# W1209_PIC.net
KiCad netlist of a schematic drawn in EAGLE
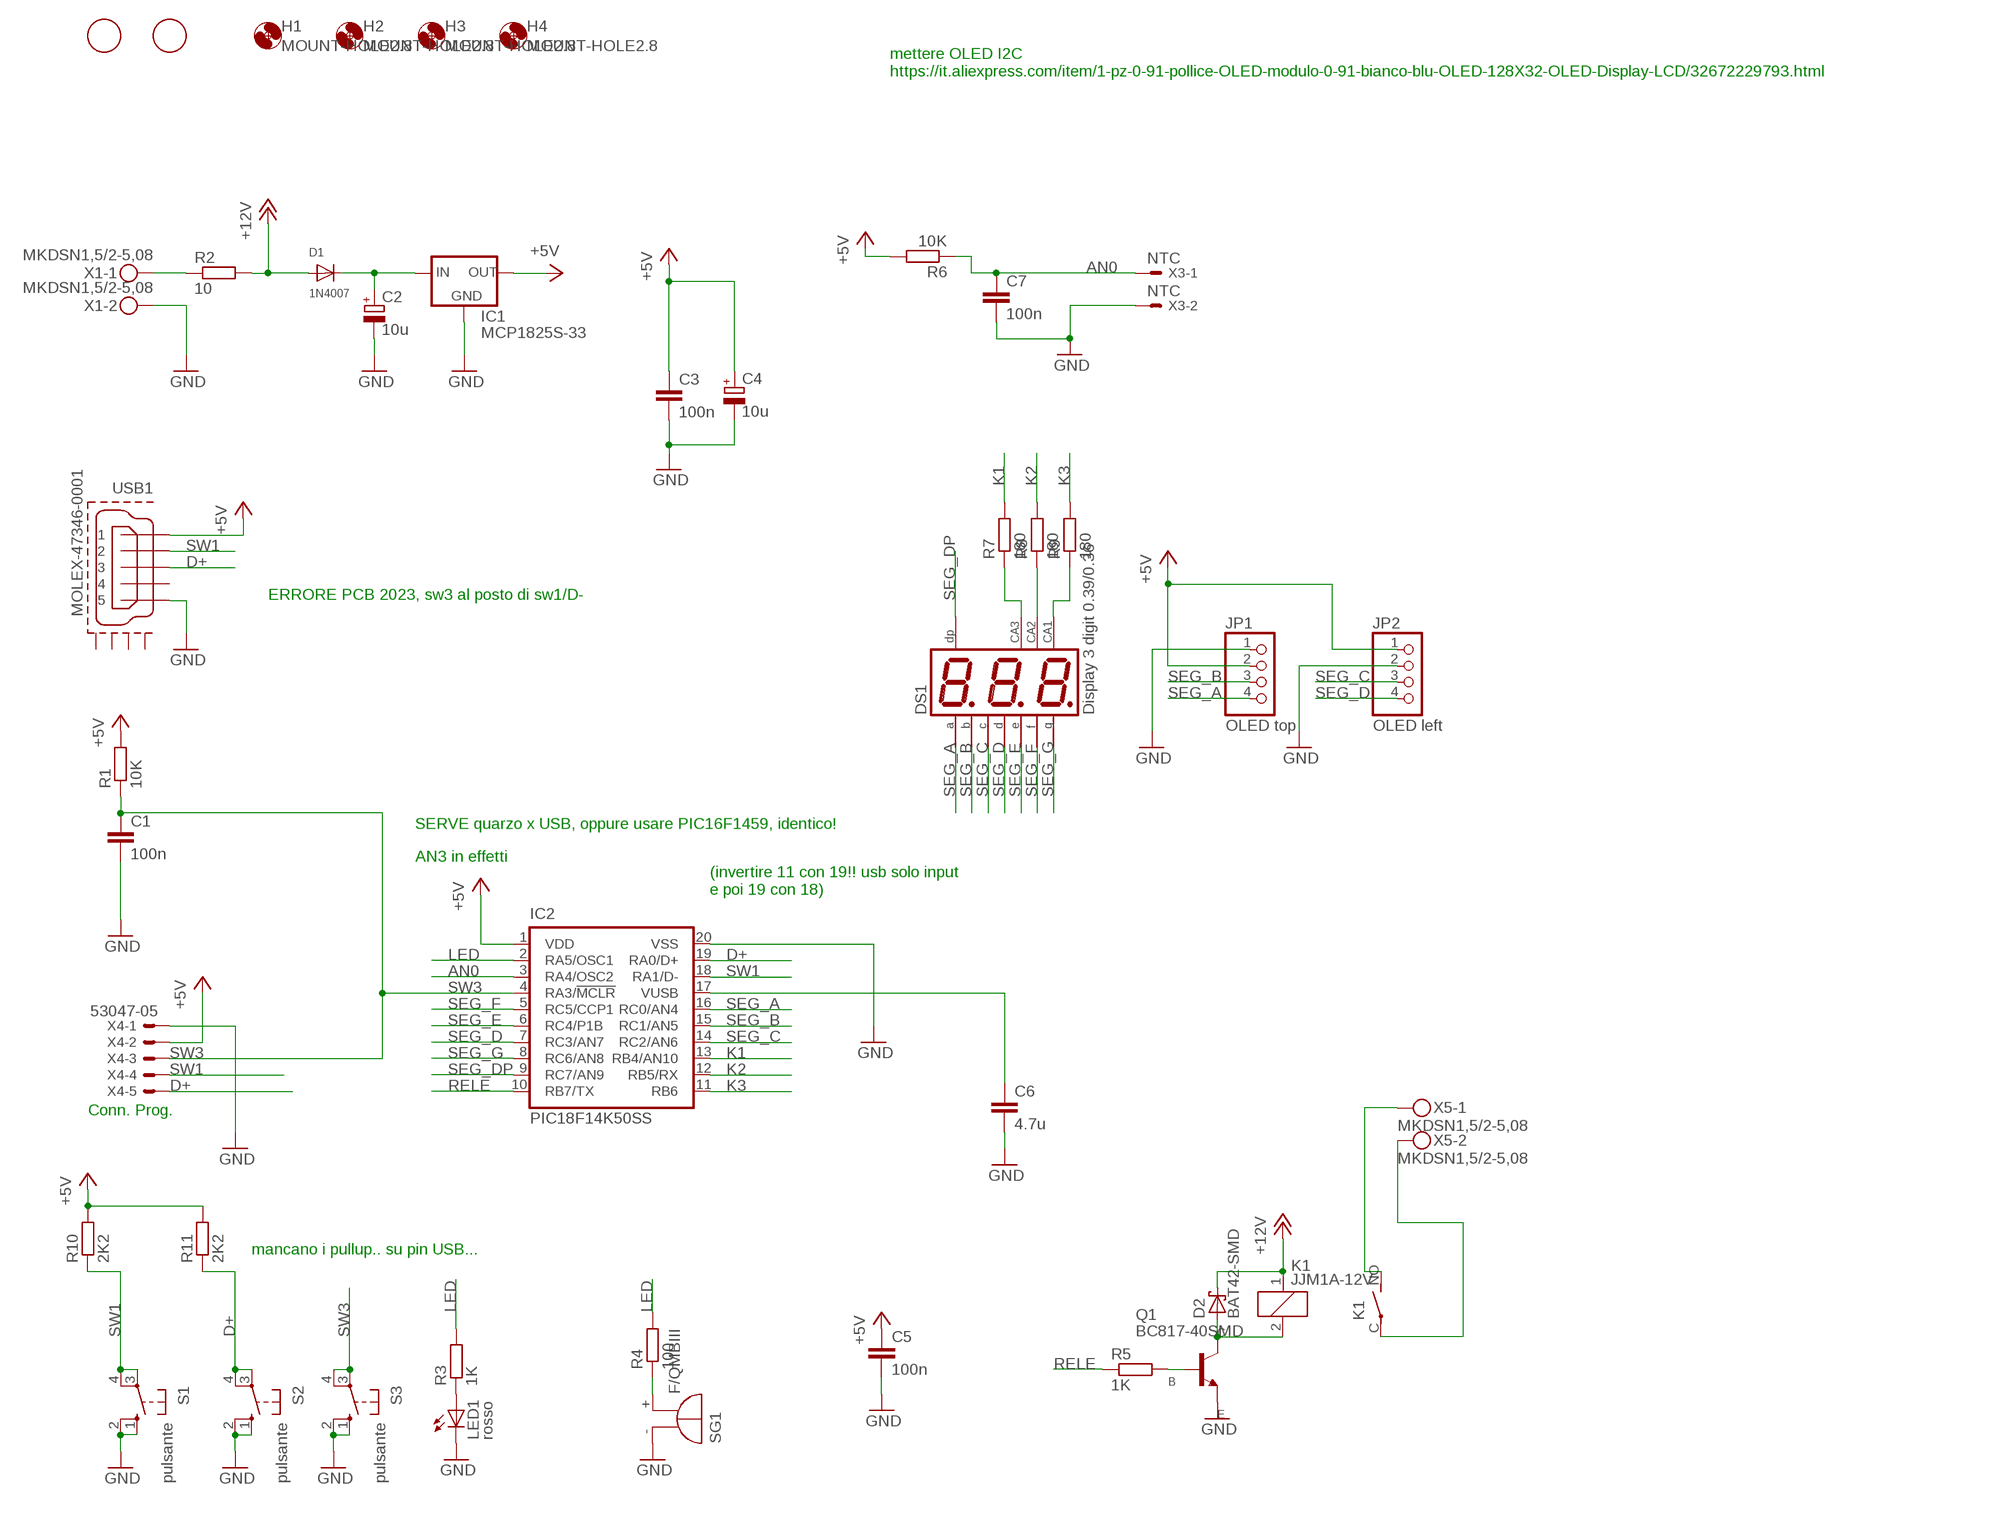
[diagram p0: schematic, sheet 1]

(export (version "E")
  (design (tool "Eeschema 10.0.6"))
  (components
    (comp (ref "C1")
      (value "100n")
      (footprint "eagle-import:C0805")
      (libsource (lib "eagle-import") (part "C-EUC0805"))
    )
    (comp (ref "C2")
      (value "10u")
      (footprint "eagle-import:SMC_C")
      (libsource (lib "eagle-import") (part "CPOL-EUSMCC"))
    )
    (comp (ref "C3")
      (value "100n")
      (footprint "eagle-import:C0805")
      (libsource (lib "eagle-import") (part "C-EUC0805"))
    )
    (comp (ref "C4")
      (value "10u")
      (footprint "eagle-import:SMC_B")
      (libsource (lib "eagle-import") (part "CPOL-EUSMCB"))
    )
    (comp (ref "C5")
      (value "100n")
      (footprint "eagle-import:C0805")
      (libsource (lib "eagle-import") (part "C-EUC0805"))
    )
    (comp (ref "C6")
      (value "4.7u")
      (footprint "eagle-import:C1206")
      (libsource (lib "eagle-import") (part "C-EUC1206"))
    )
    (comp (ref "C7")
      (value "100n")
      (footprint "eagle-import:C0805")
      (libsource (lib "eagle-import") (part "C-EUC0805"))
    )
    (comp (ref "D1")
      (value "1N4007")
      (footprint "eagle-import:SMADIODE")
      (libsource (lib "eagle-import") (part "DIODESMA"))
    )
    (comp (ref "D2")
      (value "BAT42-SMD")
      (footprint "eagle-import:DO214AC")
      (libsource (lib "eagle-import") (part "BAT42-SMD"))
    )
    (comp (ref "DS1")
      (value "Display 3 digit 0.39/0.36")
      (footprint "eagle-import:KLT36XX")
      (libsource (lib "eagle-import") (part "KLT36XX"))
    )
    (comp (ref "F1")
      (value "FIDUCIAL")
      (footprint "eagle-import:FIDUCIAL_1MM")
      (libsource (lib "eagle-import") (part "FIDUCIAL"))
    )
    (comp (ref "F2")
      (value "FIDUCIAL")
      (footprint "eagle-import:FIDUCIAL_1MM")
      (libsource (lib "eagle-import") (part "FIDUCIAL"))
    )
    (comp (ref "H1")
      (value "MOUNT-HOLE2.8")
      (footprint "eagle-import:2,8")
      (libsource (lib "eagle-import") (part "MOUNT-HOLE2.8"))
    )
    (comp (ref "H2")
      (value "MOUNT-HOLE2.8")
      (footprint "eagle-import:2,8")
      (libsource (lib "eagle-import") (part "MOUNT-HOLE2.8"))
    )
    (comp (ref "H3")
      (value "MOUNT-HOLE2.8")
      (footprint "eagle-import:2,8")
      (libsource (lib "eagle-import") (part "MOUNT-HOLE2.8"))
    )
    (comp (ref "H4")
      (value "MOUNT-HOLE2.8")
      (footprint "eagle-import:2,8")
      (libsource (lib "eagle-import") (part "MOUNT-HOLE2.8"))
    )
    (comp (ref "IC1")
      (value "MCP1825S-33")
      (footprint "eagle-import:SOT223")
      (libsource (lib "eagle-import") (part "MCP1825SSOT223"))
    )
    (comp (ref "IC2")
      (value "PIC18F14K50SS")
      (footprint "eagle-import:SS20")
      (libsource (lib "eagle-import") (part "PIC18F14K50SS"))
    )
    (comp (ref "JP1")
      (value "OLED top")
      (footprint "eagle-import:1X04")
      (libsource (lib "eagle-import") (part "PINHD-1X4"))
    )
    (comp (ref "JP2")
      (value "OLED left")
      (footprint "eagle-import:1X04")
      (libsource (lib "eagle-import") (part "PINHD-1X4"))
    )
    (comp (ref "K1")
      (value "JJM1A-12V")
      (footprint "eagle-import:JJM1A")
      (libsource (lib "eagle-import") (part "JJM1A-12V"))
    )
    (comp (ref "LED1")
      (value "rosso")
      (footprint "eagle-import:LD260")
      (libsource (lib "eagle-import") (part "LEDLD260"))
    )
    (comp (ref "Q1")
      (value "BC817-40SMD")
      (footprint "eagle-import:SOT23-BEC")
      (libsource (lib "eagle-import") (part "BC817SMD-40"))
    )
    (comp (ref "R1")
      (value "10K")
      (footprint "eagle-import:R0805")
      (libsource (lib "eagle-import") (part "R-EU_R0805"))
    )
    (comp (ref "R2")
      (value "10")
      (footprint "eagle-import:R2512")
      (libsource (lib "eagle-import") (part "R-EU_R2512"))
    )
    (comp (ref "R3")
      (value "1K")
      (footprint "eagle-import:R0805")
      (libsource (lib "eagle-import") (part "R-EU_R0805"))
    )
    (comp (ref "R4")
      (value "100")
      (footprint "eagle-import:R0805")
      (libsource (lib "eagle-import") (part "R-EU_R0805"))
    )
    (comp (ref "R5")
      (value "1K")
      (footprint "eagle-import:R0805")
      (libsource (lib "eagle-import") (part "R-EU_R0805"))
    )
    (comp (ref "R6")
      (value "10K")
      (footprint "eagle-import:R0805")
      (libsource (lib "eagle-import") (part "R-EU_R0805"))
    )
    (comp (ref "R7")
      (value "180")
      (footprint "eagle-import:R0805")
      (libsource (lib "eagle-import") (part "R-EU_R0805"))
    )
    (comp (ref "R8")
      (value "180")
      (footprint "eagle-import:R0805")
      (libsource (lib "eagle-import") (part "R-EU_R0805"))
    )
    (comp (ref "R9")
      (value "180")
      (footprint "eagle-import:R0805")
      (libsource (lib "eagle-import") (part "R-EU_R0805"))
    )
    (comp (ref "R10")
      (value "2K2")
      (footprint "eagle-import:R0805")
      (libsource (lib "eagle-import") (part "R-EU_R0805"))
    )
    (comp (ref "R11")
      (value "2K2")
      (footprint "eagle-import:R0805")
      (libsource (lib "eagle-import") (part "R-EU_R0805"))
    )
    (comp (ref "S1")
      (value "pulsante")
      (footprint "eagle-import:B3F-10XX")
      (fields (field (name "MPN") "B3F-1000"))
      (libsource (lib "eagle-import") (part "10-XX"))
    )
    (comp (ref "S2")
      (value "pulsante")
      (footprint "eagle-import:B3F-10XX")
      (fields (field (name "MPN") "B3F-1000"))
      (libsource (lib "eagle-import") (part "10-XX"))
    )
    (comp (ref "S3")
      (value "pulsante")
      (footprint "eagle-import:B3F-10XX")
      (fields (field (name "MPN") "B3F-1000"))
      (libsource (lib "eagle-import") (part "10-XX"))
    )
    (comp (ref "SG1")
      (value "F/QMBIII")
      (footprint "eagle-import:F_QMBIII")
      (libsource (lib "eagle-import") (part "F/QMBIII"))
    )
    (comp (ref "USB1")
      (value "MOLEX-47346-0001")
      (footprint "eagle-import:MOLEX-47364-0001")
      (libsource (lib "eagle-import") (part "MOLEX-47346-0001"))
    )
    (comp (ref "X1")
      (value "MKDSN1,5/2-5,08")
      (footprint "eagle-import:MKDSN1,5_2-5,08")
      (libsource (lib "eagle-import") (part "MKDSN1,5/2-5,08"))
    )
    (comp (ref "X3")
      (value "NTC")
      (footprint "eagle-import:KK-156-2")
      (libsource (lib "eagle-import") (part "KK-156-2"))
    )
    (comp (ref "X4")
      (value "53047-05")
      (footprint "eagle-import:53047-05")
      (fields (field (name "MF") "MOLEX") (field (name "MPN") "53047-0510"))
      (libsource (lib "eagle-import") (part "53?-05047"))
    )
    (comp (ref "X5")
      (value "MKDSN1,5/2-5,08")
      (footprint "eagle-import:MKDSN1,5_2-5,08")
      (libsource (lib "eagle-import") (part "MKDSN1,5/2-5,08"))
    )
  )
  (nets
    (net (code "1") (name "+5V") (class "Default")
      (node (ref "C3") (pin "1") (pinfunction "1_1") (pintype "passive"))
      (node (ref "C4") (pin "+") (pinfunction "+_+") (pintype "passive"))
      (node (ref "C5") (pin "1") (pinfunction "1_1") (pintype "passive"))
      (node (ref "IC1") (pin "3") (pinfunction "OUT_3") (pintype "passive"))
      (node (ref "IC2") (pin "1") (pinfunction "VDD_1") (pintype "power_in"))
      (node (ref "JP1") (pin "2") (pinfunction "2_2") (pintype "passive"))
      (node (ref "JP2") (pin "1") (pinfunction "1_1") (pintype "passive"))
      (node (ref "R1") (pin "2") (pinfunction "2_2") (pintype "passive"))
      (node (ref "R10") (pin "2") (pinfunction "2_2") (pintype "passive"))
      (node (ref "R11") (pin "2") (pinfunction "2_2") (pintype "passive"))
      (node (ref "R6") (pin "2") (pinfunction "2_2") (pintype "passive"))
      (node (ref "USB1") (pin "1") (pinfunction "1_1") (pintype "input"))
      (node (ref "X4") (pin "2") (pinfunction "S_2") (pintype "passive"))
    )
    (net (code "2") (name "+12V") (class "Default")
      (node (ref "D1") (pin "A") (pinfunction "A_A") (pintype "passive"))
      (node (ref "D2") (pin "C") (pinfunction "C_C") (pintype "passive"))
      (node (ref "K1") (pin "1") (pinfunction "1_1") (pintype "passive"))
      (node (ref "R2") (pin "2") (pinfunction "2_2") (pintype "passive"))
    )
    (net (code "3") (name "/AN0") (class "Default")
      (node (ref "C7") (pin "1") (pinfunction "1_1") (pintype "passive"))
      (node (ref "IC2") (pin "3") (pinfunction "RA4/OSC2_3") (pintype "bidirectional"))
      (node (ref "R6") (pin "1") (pinfunction "1_1") (pintype "passive"))
      (node (ref "X3") (pin "1") (pinfunction "S_1") (pintype "passive"))
    )
    (net (code "4") (name "/D+") (class "Default")
      (node (ref "IC2") (pin "19") (pinfunction "RA0/D+_19") (pintype "bidirectional"))
      (node (ref "R11") (pin "1") (pinfunction "1_1") (pintype "passive"))
      (node (ref "S2") (pin "3") (pinfunction "P_3") (pintype "passive"))
      (node (ref "S2") (pin "4") (pinfunction "P1_4") (pintype "passive"))
      (node (ref "USB1") (pin "3") (pinfunction "3_3") (pintype "input"))
      (node (ref "X4") (pin "5") (pinfunction "S_5") (pintype "passive"))
    )
    (net (code "5") (name "/K1") (class "Default")
      (node (ref "IC2") (pin "13") (pinfunction "RB4/AN10_13") (pintype "bidirectional"))
      (node (ref "R7") (pin "2") (pinfunction "2_2") (pintype "passive"))
    )
    (net (code "6") (name "/K2") (class "Default")
      (node (ref "IC2") (pin "12") (pinfunction "RB5/RX_12") (pintype "bidirectional"))
      (node (ref "R8") (pin "2") (pinfunction "2_2") (pintype "passive"))
    )
    (net (code "7") (name "/K3") (class "Default")
      (node (ref "IC2") (pin "11") (pinfunction "RB6_11") (pintype "bidirectional"))
      (node (ref "R9") (pin "2") (pinfunction "2_2") (pintype "passive"))
    )
    (net (code "8") (name "/LED") (class "Default")
      (node (ref "IC2") (pin "2") (pinfunction "RA5/OSC1_2") (pintype "bidirectional"))
      (node (ref "R3") (pin "2") (pinfunction "2_2") (pintype "passive"))
      (node (ref "R4") (pin "2") (pinfunction "2_2") (pintype "passive"))
    )
    (net (code "9") (name "/RELE") (class "Default")
      (node (ref "IC2") (pin "10") (pinfunction "RB7/TX_10") (pintype "bidirectional"))
      (node (ref "R5") (pin "1") (pinfunction "1_1") (pintype "passive"))
    )
    (net (code "10") (name "/SEG_A") (class "Default")
      (node (ref "DS1") (pin "P$11") (pinfunction "A_P$11") (pintype "passive"))
      (node (ref "IC2") (pin "16") (pinfunction "RC0/AN4_16") (pintype "bidirectional"))
      (node (ref "JP1") (pin "4") (pinfunction "4_4") (pintype "passive"))
    )
    (net (code "11") (name "/SEG_B") (class "Default")
      (node (ref "DS1") (pin "P$7") (pinfunction "B_P$7") (pintype "passive"))
      (node (ref "IC2") (pin "15") (pinfunction "RC1/AN5_15") (pintype "bidirectional"))
      (node (ref "JP1") (pin "3") (pinfunction "3_3") (pintype "passive"))
    )
    (net (code "12") (name "/SEG_C") (class "Default")
      (node (ref "DS1") (pin "P$4") (pinfunction "C_P$4") (pintype "passive"))
      (node (ref "IC2") (pin "14") (pinfunction "RC2/AN6_14") (pintype "bidirectional"))
      (node (ref "JP2") (pin "3") (pinfunction "3_3") (pintype "passive"))
    )
    (net (code "13") (name "/SEG_D") (class "Default")
      (node (ref "DS1") (pin "P$2") (pinfunction "D_P$2") (pintype "passive"))
      (node (ref "IC2") (pin "7") (pinfunction "RC3/AN7_7") (pintype "bidirectional"))
      (node (ref "JP2") (pin "4") (pinfunction "4_4") (pintype "passive"))
    )
    (net (code "14") (name "/SEG_DP") (class "Default")
      (node (ref "DS1") (pin "P$3") (pinfunction "DP_P$3") (pintype "passive"))
      (node (ref "IC2") (pin "9") (pinfunction "RC7/AN9_9") (pintype "bidirectional"))
    )
    (net (code "15") (name "/SEG_E") (class "Default")
      (node (ref "DS1") (pin "P$1") (pinfunction "E_P$1") (pintype "passive"))
      (node (ref "IC2") (pin "6") (pinfunction "RC4/P1B_6") (pintype "bidirectional"))
    )
    (net (code "16") (name "/SEG_F") (class "Default")
      (node (ref "DS1") (pin "P$10") (pinfunction "F_P$10") (pintype "passive"))
      (node (ref "IC2") (pin "5") (pinfunction "RC5/CCP1_5") (pintype "bidirectional"))
    )
    (net (code "17") (name "/SEG_G") (class "Default")
      (node (ref "DS1") (pin "P$5") (pinfunction "G_P$5") (pintype "passive"))
      (node (ref "IC2") (pin "8") (pinfunction "RC6/AN8_8") (pintype "bidirectional"))
    )
    (net (code "18") (name "/SW1") (class "Default")
      (node (ref "IC2") (pin "18") (pinfunction "RA1/D-_18") (pintype "bidirectional"))
      (node (ref "R10") (pin "1") (pinfunction "1_1") (pintype "passive"))
      (node (ref "S1") (pin "3") (pinfunction "P_3") (pintype "passive"))
      (node (ref "S1") (pin "4") (pinfunction "P1_4") (pintype "passive"))
      (node (ref "USB1") (pin "2") (pinfunction "2_2") (pintype "input"))
      (node (ref "X4") (pin "4") (pinfunction "S_4") (pintype "passive"))
    )
    (net (code "19") (name "/SW3") (class "Default")
      (node (ref "C1") (pin "1") (pinfunction "1_1") (pintype "passive"))
      (node (ref "IC2") (pin "4") (pinfunction "RA3/~{MCLR}_4") (pintype "bidirectional"))
      (node (ref "R1") (pin "1") (pinfunction "1_1") (pintype "passive"))
      (node (ref "S3") (pin "3") (pinfunction "P_3") (pintype "passive"))
      (node (ref "S3") (pin "4") (pinfunction "P1_4") (pintype "passive"))
      (node (ref "X4") (pin "3") (pinfunction "S_3") (pintype "passive"))
    )
    (net (code "20") (name "GND") (class "Default")
      (node (ref "C1") (pin "2") (pinfunction "2_2") (pintype "passive"))
      (node (ref "C2") (pin "-") (pinfunction "-_-") (pintype "passive"))
      (node (ref "C3") (pin "2") (pinfunction "2_2") (pintype "passive"))
      (node (ref "C4") (pin "-") (pinfunction "-_-") (pintype "passive"))
      (node (ref "C5") (pin "2") (pinfunction "2_2") (pintype "passive"))
      (node (ref "C6") (pin "2") (pinfunction "2_2") (pintype "passive"))
      (node (ref "C7") (pin "2") (pinfunction "2_2") (pintype "passive"))
      (node (ref "IC1") (pin "2") (pinfunction "GND_2") (pintype "input"))
      (node (ref "IC1") (pin "4") (pinfunction "GND_4") (pintype "input"))
      (node (ref "IC2") (pin "20") (pinfunction "VSS_20") (pintype "power_in"))
      (node (ref "JP1") (pin "1") (pinfunction "1_1") (pintype "passive"))
      (node (ref "JP2") (pin "2") (pinfunction "2_2") (pintype "passive"))
      (node (ref "LED1") (pin "K") (pinfunction "C_K") (pintype "passive"))
      (node (ref "Q1") (pin "E") (pinfunction "E_E") (pintype "passive"))
      (node (ref "S1") (pin "1") (pinfunction "S_1") (pintype "passive"))
      (node (ref "S1") (pin "2") (pinfunction "S1_2") (pintype "passive"))
      (node (ref "S2") (pin "1") (pinfunction "S_1") (pintype "passive"))
      (node (ref "S2") (pin "2") (pinfunction "S1_2") (pintype "passive"))
      (node (ref "S3") (pin "1") (pinfunction "S_1") (pintype "passive"))
      (node (ref "S3") (pin "2") (pinfunction "S1_2") (pintype "passive"))
      (node (ref "SG1") (pin "-") (pinfunction "+_-") (pintype "passive"))
      (node (ref "USB1") (pin "5") (pinfunction "5_5") (pintype "input"))
      (node (ref "X1") (pin "2") (pinfunction "KL_2") (pintype "passive"))
      (node (ref "X3") (pin "2") (pinfunction "S_2") (pintype "passive"))
      (node (ref "X4") (pin "1") (pinfunction "S_1") (pintype "passive"))
    )
    (net (code "21") (name "Net-(D2-PadA)") (class "Default")
      (node (ref "D2") (pin "A") (pinfunction "A_A") (pintype "passive"))
      (node (ref "K1") (pin "2") (pinfunction "2_2") (pintype "passive"))
      (node (ref "Q1") (pin "C") (pinfunction "C_C") (pintype "passive"))
    )
    (net (code "22") (name "Net-(DS1-CA-PadP$8)") (class "Default")
      (node (ref "DS1") (pin "P$8") (pinfunction "CA_P$8") (pintype "passive"))
      (node (ref "R9") (pin "1") (pinfunction "1_1") (pintype "passive"))
    )
    (net (code "23") (name "Net-(DS1-CA-PadP$9)") (class "Default")
      (node (ref "DS1") (pin "P$9") (pinfunction "CA_P$9") (pintype "passive"))
      (node (ref "R8") (pin "1") (pinfunction "1_1") (pintype "passive"))
    )
    (net (code "24") (name "Net-(DS1-CA-PadP$12)") (class "Default")
      (node (ref "DS1") (pin "P$12") (pinfunction "CA_P$12") (pintype "passive"))
      (node (ref "R7") (pin "1") (pinfunction "1_1") (pintype "passive"))
    )
    (net (code "25") (name "Net-(IC1-IN)") (class "Default")
      (node (ref "C2") (pin "+") (pinfunction "+_+") (pintype "passive"))
      (node (ref "D1") (pin "C") (pinfunction "C_C") (pintype "passive"))
      (node (ref "IC1") (pin "1") (pinfunction "IN_1") (pintype "input"))
    )
    (net (code "26") (name "Net-(IC2-VUSB)") (class "Default")
      (node (ref "C6") (pin "1") (pinfunction "1_1") (pintype "passive"))
      (node (ref "IC2") (pin "17") (pinfunction "VUSB_17") (pintype "bidirectional"))
    )
    (net (code "27") (name "Net-(K1B-P)") (class "Default")
      (node (ref "K1") (pin "C") (pinfunction "P_C") (pintype "passive"))
      (node (ref "X5") (pin "2") (pinfunction "KL_2") (pintype "passive"))
    )
    (net (code "28") (name "Net-(K1B-S)") (class "Default")
      (node (ref "K1") (pin "NO") (pinfunction "S_NO") (pintype "passive"))
      (node (ref "X5") (pin "1") (pinfunction "KL_1") (pintype "passive"))
    )
    (net (code "29") (name "Net-(LED1-PadA)") (class "Default")
      (node (ref "LED1") (pin "A") (pinfunction "A_A") (pintype "passive"))
      (node (ref "R3") (pin "1") (pinfunction "1_1") (pintype "passive"))
    )
    (net (code "30") (name "Net-(Q1-PadB)") (class "Default")
      (node (ref "Q1") (pin "B") (pinfunction "B_B") (pintype "passive"))
      (node (ref "R5") (pin "2") (pinfunction "2_2") (pintype "passive"))
    )
    (net (code "31") (name "Net-(SG1--)") (class "Default")
      (node (ref "R4") (pin "1") (pinfunction "1_1") (pintype "passive"))
      (node (ref "SG1") (pin "+") (pinfunction "-_+") (pintype "passive"))
    )
    (net (code "32") (name "Net-(X1A-KL)") (class "Default")
      (node (ref "R2") (pin "1") (pinfunction "1_1") (pintype "passive"))
      (node (ref "X1") (pin "1") (pinfunction "KL_1") (pintype "passive"))
    )
    (net (code "33") (name "unconnected-(USB1-Pad4)") (class "Default")
      (node (ref "USB1") (pin "4") (pinfunction "4_4") (pintype "input"))
    )
    (net (code "34") (name "unconnected-(USB1-PadGND1)") (class "Default")
      (node (ref "USB1") (pin "GND1") (pinfunction "GND1_GND1") (pintype "bidirectional"))
    )
    (net (code "35") (name "unconnected-(USB1-PadGND2)") (class "Default")
      (node (ref "USB1") (pin "GND2") (pinfunction "GND2_GND2") (pintype "bidirectional"))
    )
    (net (code "36") (name "unconnected-(USB1-PadGND3)") (class "Default")
      (node (ref "USB1") (pin "GND3") (pinfunction "GND3_GND3") (pintype "bidirectional"))
    )
    (net (code "37") (name "unconnected-(USB1-PadGND4)") (class "Default")
      (node (ref "USB1") (pin "GND4") (pinfunction "GND4_GND4") (pintype "bidirectional"))
    )
  )
)
